# Schnittstelle_Swissphone.net
KiCad netlist of a schematic drawn in EAGLE
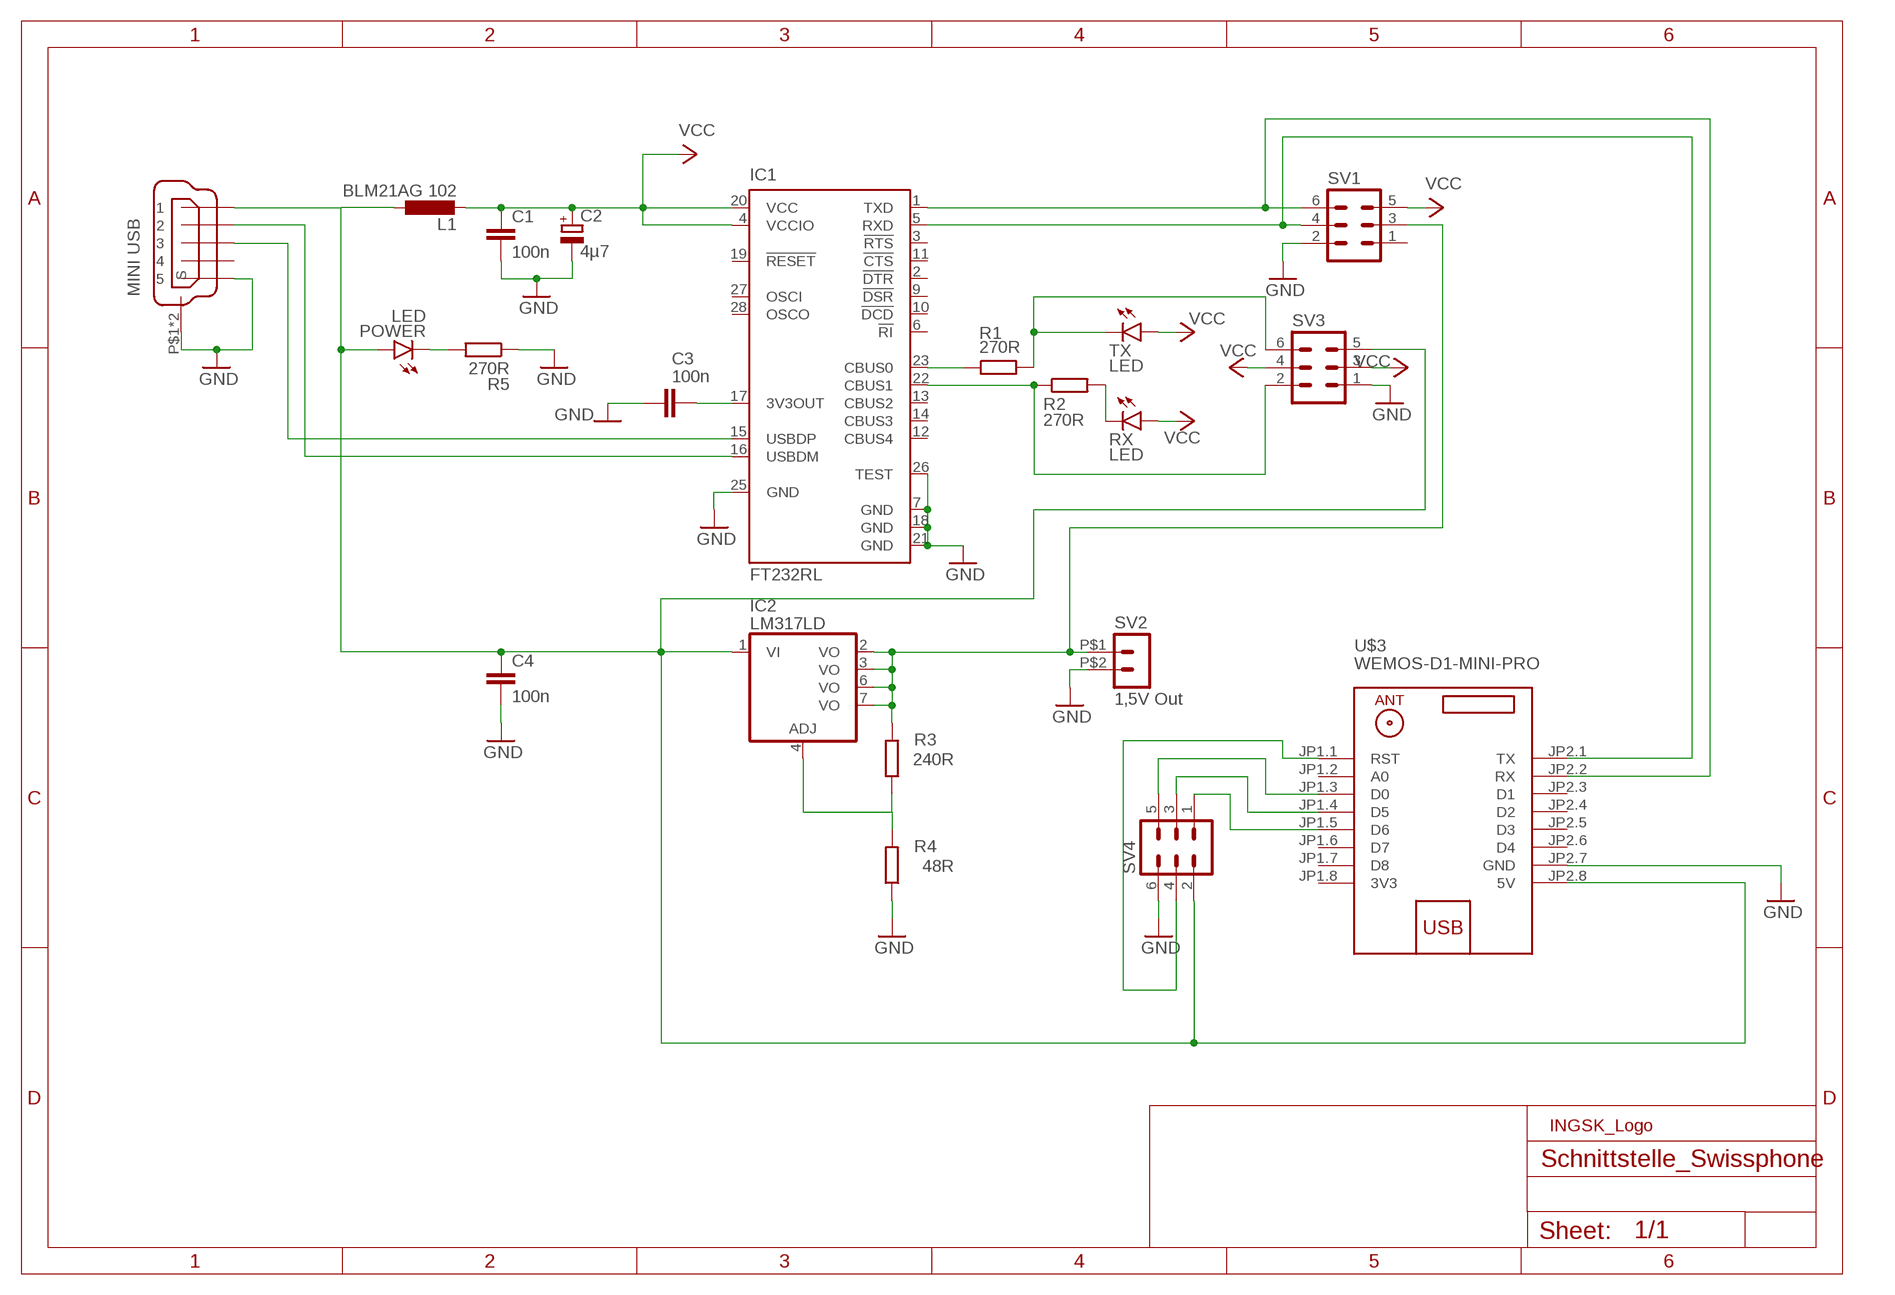
[diagram p0: schematic, sheet 1]

(export (version "E")
  (design (tool "Eeschema 10.0.6"))
  (components
    (comp (ref "C1")
      (value "100n")
      (footprint "eagle-import:C0603")
      (libsource (lib "eagle-import") (part "C-EUC0603"))
    )
    (comp (ref "C2")
      (value "4µ7")
      (footprint "eagle-import:A_3216-18W")
      (libsource (lib "eagle-import") (part "CPOL-EUA/3216-18W"))
    )
    (comp (ref "C3")
      (value "100n")
      (footprint "eagle-import:C0603")
      (libsource (lib "eagle-import") (part "C-EUC0603"))
    )
    (comp (ref "C4")
      (value "100n")
      (footprint "eagle-import:C0603")
      (libsource (lib "eagle-import") (part "C-EUC0603"))
    )
    (comp (ref "IC1")
      (value "FT232RL")
      (footprint "eagle-import:SSOP28")
      (libsource (lib "eagle-import") (part "FT232RL"))
    )
    (comp (ref "IC2")
      (value "LM317LD")
      (footprint "eagle-import:SO08")
      (libsource (lib "eagle-import") (part "LM317LD"))
    )
    (comp (ref "L1")
      (value "BLM21AG 102")
      (footprint "eagle-import:L2012C")
      (libsource (lib "eagle-import") (part "L-EUL2012C"))
    )
    (comp (ref "POWER")
      (value "LED")
      (footprint "eagle-import:LED3MM")
      (libsource (lib "eagle-import") (part "LED3MM"))
    )
    (comp (ref "R1")
      (value "270R")
      (footprint "eagle-import:R0603")
      (libsource (lib "eagle-import") (part "R-EU_R0603"))
    )
    (comp (ref "R2")
      (value "270R")
      (footprint "eagle-import:R0603")
      (libsource (lib "eagle-import") (part "R-EU_R0603"))
    )
    (comp (ref "R3")
      (value "240R")
      (footprint "eagle-import:R1206")
      (libsource (lib "eagle-import") (part "R-EU_R1206"))
    )
    (comp (ref "R4")
      (value "48R")
      (footprint "eagle-import:R1206")
      (libsource (lib "eagle-import") (part "R-EU_R1206"))
    )
    (comp (ref "R5")
      (value "270R")
      (footprint "eagle-import:R0603")
      (libsource (lib "eagle-import") (part "R-EU_R0603"))
    )
    (comp (ref "RX")
      (value "LED")
      (footprint "eagle-import:LED3MM")
      (libsource (lib "eagle-import") (part "LED3MM"))
    )
    (comp (ref "SV1")
      (value "ML6")
      (footprint "eagle-import:ML6")
      (libsource (lib "eagle-import") (part "ML6"))
    )
    (comp (ref "SV2")
      (value "1,5V Out")
      (footprint "eagle-import:43650-0200")
      (libsource (lib "eagle-import") (part "HEADER_POS2_?43650-0200"))
    )
    (comp (ref "SV3")
      (value "ML6")
      (footprint "eagle-import:ML6")
      (libsource (lib "eagle-import") (part "ML6"))
    )
    (comp (ref "SV4")
      (value "ML6")
      (footprint "eagle-import:ML6")
      (libsource (lib "eagle-import") (part "ML6"))
    )
    (comp (ref "TX")
      (value "LED")
      (footprint "eagle-import:LED3MM")
      (libsource (lib "eagle-import") (part "LED3MM"))
    )
    (comp (ref "U$1")
      (value "MINI USB")
      (footprint "eagle-import:USBBWM")
      (libsource (lib "eagle-import") (part "USBBWM"))
    )
    (comp (ref "U$2")
      (value "SK")
      (footprint "eagle-import:INGSK")
      (libsource (lib "eagle-import") (part "SK"))
    )
    (comp (ref "U$3")
      (value "WEMOS-D1-MINI-PRO")
      (footprint "eagle-import:WEMOS-D1-MINI-PRO")
      (libsource (lib "eagle-import") (part "WEMOS-D1-MINI-PRO"))
    )
  )
  (nets
    (net (code "1") (name "/3V3") (class "Default")
      (node (ref "U$3") (pin "JP1.8") (pinfunction "3V3_JP1.8") (pintype "power_in"))
    )
    (net (code "2") (name "GND") (class "Default")
      (node (ref "C1") (pin "2") (pinfunction "2_2") (pintype "passive"))
      (node (ref "C2") (pin "-") (pinfunction "-_-") (pintype "passive"))
      (node (ref "C3") (pin "2") (pinfunction "2_2") (pintype "passive"))
      (node (ref "C4") (pin "2") (pinfunction "2_2") (pintype "passive"))
      (node (ref "IC1") (pin "18") (pinfunction "GND_18") (pintype "power_in"))
      (node (ref "IC1") (pin "21") (pinfunction "GND_21") (pintype "power_in"))
      (node (ref "IC1") (pin "25") (pinfunction "GND_25") (pintype "power_in"))
      (node (ref "IC1") (pin "26") (pinfunction "TEST_26") (pintype "input"))
      (node (ref "IC1") (pin "7") (pinfunction "GND_7") (pintype "power_in"))
      (node (ref "R4") (pin "1") (pinfunction "1_1") (pintype "passive"))
      (node (ref "R5") (pin "1") (pinfunction "1_1") (pintype "passive"))
      (node (ref "SV1") (pin "2") (pinfunction "2_2") (pintype "passive"))
      (node (ref "SV2") (pin "P$2") (pinfunction "2_P$2") (pintype "passive"))
      (node (ref "SV3") (pin "1") (pinfunction "1_1") (pintype "passive"))
      (node (ref "SV4") (pin "6") (pinfunction "6_6") (pintype "passive"))
      (node (ref "U$1") (pin "P$1") (pinfunction "S_P$1") (pintype "bidirectional"))
      (node (ref "U$1") (pin "P$2") (pinfunction "S_P$2") (pintype "bidirectional"))
      (node (ref "U$1") (pin "P$3") (pinfunction "5_P$3") (pintype "passive"))
      (node (ref "U$3") (pin "JP2.7") (pinfunction "GND_JP2.7") (pintype "power_in"))
    )
    (net (code "3") (name "Net-(IC1-3V3OUT)") (class "Default")
      (node (ref "C3") (pin "1") (pinfunction "1_1") (pintype "passive"))
      (node (ref "IC1") (pin "17") (pinfunction "3V3OUT_17") (pintype "output"))
    )
    (net (code "4") (name "Net-(IC1-CBUS0)") (class "Default")
      (node (ref "IC1") (pin "23") (pinfunction "CBUS0_23") (pintype "bidirectional"))
      (node (ref "R1") (pin "1") (pinfunction "1_1") (pintype "passive"))
    )
    (net (code "5") (name "Net-(IC1-CBUS1)") (class "Default")
      (node (ref "IC1") (pin "22") (pinfunction "CBUS1_22") (pintype "bidirectional"))
      (node (ref "R2") (pin "1") (pinfunction "1_1") (pintype "passive"))
      (node (ref "SV3") (pin "2") (pinfunction "2_2") (pintype "passive"))
    )
    (net (code "6") (name "Net-(IC1-RXD)") (class "Default")
      (node (ref "IC1") (pin "5") (pinfunction "RXD_5") (pintype "input"))
      (node (ref "SV1") (pin "4") (pinfunction "4_4") (pintype "passive"))
      (node (ref "U$3") (pin "JP2.1") (pinfunction "TX_JP2.1") (pintype "bidirectional"))
    )
    (net (code "7") (name "Net-(IC1-TXD)") (class "Default")
      (node (ref "IC1") (pin "1") (pinfunction "TXD_1") (pintype "output"))
      (node (ref "SV1") (pin "6") (pinfunction "6_6") (pintype "passive"))
      (node (ref "U$3") (pin "JP2.2") (pinfunction "RX_JP2.2") (pintype "bidirectional"))
    )
    (net (code "8") (name "Net-(IC1-USBDM)") (class "Default")
      (node (ref "IC1") (pin "16") (pinfunction "USBDM_16") (pintype "bidirectional"))
      (node (ref "U$1") (pin "P$6") (pinfunction "2_P$6") (pintype "passive"))
    )
    (net (code "9") (name "Net-(IC1-USBDP)") (class "Default")
      (node (ref "IC1") (pin "15") (pinfunction "USBDP_15") (pintype "bidirectional"))
      (node (ref "U$1") (pin "P$5") (pinfunction "3_P$5") (pintype "passive"))
    )
    (net (code "10") (name "Net-(IC2-ADJ)") (class "Default")
      (node (ref "IC2") (pin "4") (pinfunction "ADJ_4") (pintype "input"))
      (node (ref "R3") (pin "1") (pinfunction "1_1") (pintype "passive"))
      (node (ref "R4") (pin "2") (pinfunction "2_2") (pintype "passive"))
    )
    (net (code "11") (name "Net-(IC2-VI)") (class "Default")
      (node (ref "C4") (pin "1") (pinfunction "1_1") (pintype "passive"))
      (node (ref "IC2") (pin "1") (pinfunction "VI_1") (pintype "input"))
      (node (ref "L1") (pin "1") (pinfunction "1_1") (pintype "passive"))
      (node (ref "POWER") (pin "A") (pinfunction "A_A") (pintype "passive"))
      (node (ref "SV3") (pin "5") (pinfunction "5_5") (pintype "passive"))
      (node (ref "SV4") (pin "2") (pinfunction "2_2") (pintype "passive"))
      (node (ref "U$1") (pin "P$7") (pinfunction "1_P$7") (pintype "passive"))
      (node (ref "U$3") (pin "JP2.8") (pinfunction "5V_JP2.8") (pintype "power_in"))
    )
    (net (code "12") (name "Net-(POWER-C)") (class "Default")
      (node (ref "POWER") (pin "K") (pinfunction "C_K") (pintype "passive"))
      (node (ref "R5") (pin "2") (pinfunction "2_2") (pintype "passive"))
    )
    (net (code "13") (name "Net-(RX-C)") (class "Default")
      (node (ref "R2") (pin "2") (pinfunction "2_2") (pintype "passive"))
      (node (ref "RX") (pin "K") (pinfunction "C_K") (pintype "passive"))
    )
    (net (code "14") (name "Net-(SV2-1)") (class "Default")
      (node (ref "IC2") (pin "2") (pinfunction "VO_2") (pintype "passive"))
      (node (ref "IC2") (pin "3") (pinfunction "VO_3") (pintype "passive"))
      (node (ref "IC2") (pin "6") (pinfunction "VO_6") (pintype "passive"))
      (node (ref "IC2") (pin "7") (pinfunction "VO_7") (pintype "passive"))
      (node (ref "R3") (pin "2") (pinfunction "2_2") (pintype "passive"))
      (node (ref "SV1") (pin "3") (pinfunction "3_3") (pintype "passive"))
      (node (ref "SV2") (pin "P$1") (pinfunction "1_P$1") (pintype "passive"))
    )
    (net (code "15") (name "Net-(TX-C)") (class "Default")
      (node (ref "R1") (pin "2") (pinfunction "2_2") (pintype "passive"))
      (node (ref "SV3") (pin "6") (pinfunction "6_6") (pintype "passive"))
      (node (ref "TX") (pin "K") (pinfunction "C_K") (pintype "passive"))
    )
    (net (code "16") (name "Net-(U$3-D0)") (class "Default")
      (node (ref "SV4") (pin "5") (pinfunction "5_5") (pintype "passive"))
      (node (ref "U$3") (pin "JP1.3") (pinfunction "D0_JP1.3") (pintype "bidirectional"))
    )
    (net (code "17") (name "Net-(U$3-D5)") (class "Default")
      (node (ref "SV4") (pin "3") (pinfunction "3_3") (pintype "passive"))
      (node (ref "U$3") (pin "JP1.4") (pinfunction "D5_JP1.4") (pintype "bidirectional"))
    )
    (net (code "18") (name "Net-(U$3-D6)") (class "Default")
      (node (ref "SV4") (pin "1") (pinfunction "1_1") (pintype "passive"))
      (node (ref "U$3") (pin "JP1.5") (pinfunction "D6_JP1.5") (pintype "bidirectional"))
    )
    (net (code "19") (name "Net-(U$3-RST)") (class "Default")
      (node (ref "SV4") (pin "4") (pinfunction "4_4") (pintype "passive"))
      (node (ref "U$3") (pin "JP1.1") (pinfunction "RST_JP1.1") (pintype "bidirectional"))
    )
    (net (code "20") (name "VCC") (class "Default")
      (node (ref "C1") (pin "1") (pinfunction "1_1") (pintype "passive"))
      (node (ref "C2") (pin "+") (pinfunction "+_+") (pintype "passive"))
      (node (ref "IC1") (pin "20") (pinfunction "VCC_20") (pintype "power_in"))
      (node (ref "IC1") (pin "4") (pinfunction "VCCIO_4") (pintype "power_in"))
      (node (ref "L1") (pin "2") (pinfunction "2_2") (pintype "passive"))
      (node (ref "RX") (pin "A") (pinfunction "A_A") (pintype "passive"))
      (node (ref "SV1") (pin "5") (pinfunction "5_5") (pintype "passive"))
      (node (ref "SV3") (pin "3") (pinfunction "3_3") (pintype "passive"))
      (node (ref "SV3") (pin "4") (pinfunction "4_4") (pintype "passive"))
      (node (ref "TX") (pin "A") (pinfunction "A_A") (pintype "passive"))
    )
    (net (code "21") (name "unconnected-(IC1-CBUS2-Pad13)") (class "Default")
      (node (ref "IC1") (pin "13") (pinfunction "CBUS2_13") (pintype "bidirectional"))
    )
    (net (code "22") (name "unconnected-(IC1-CBUS3-Pad14)") (class "Default")
      (node (ref "IC1") (pin "14") (pinfunction "CBUS3_14") (pintype "bidirectional"))
    )
    (net (code "23") (name "unconnected-(IC1-CBUS4-Pad12)") (class "Default")
      (node (ref "IC1") (pin "12") (pinfunction "CBUS4_12") (pintype "bidirectional"))
    )
    (net (code "24") (name "unconnected-(IC1-OSCI-Pad27)") (class "Default")
      (node (ref "IC1") (pin "27") (pinfunction "OSCI_27") (pintype "input"))
    )
    (net (code "25") (name "unconnected-(IC1-OSCO-Pad28)") (class "Default")
      (node (ref "IC1") (pin "28") (pinfunction "OSCO_28") (pintype "output"))
    )
    (net (code "26") (name "unconnected-(IC1-~{CTS}-Pad11)") (class "Default")
      (node (ref "IC1") (pin "11") (pinfunction "~{CTS}_11") (pintype "input"))
    )
    (net (code "27") (name "unconnected-(IC1-~{DCD}-Pad10)") (class "Default")
      (node (ref "IC1") (pin "10") (pinfunction "~{DCD}_10") (pintype "input"))
    )
    (net (code "28") (name "unconnected-(IC1-~{DSR}-Pad9)") (class "Default")
      (node (ref "IC1") (pin "9") (pinfunction "~{DSR}_9") (pintype "input"))
    )
    (net (code "29") (name "unconnected-(IC1-~{DTR}-Pad2)") (class "Default")
      (node (ref "IC1") (pin "2") (pinfunction "~{DTR}_2") (pintype "output"))
    )
    (net (code "30") (name "unconnected-(IC1-~{RESET}-Pad19)") (class "Default")
      (node (ref "IC1") (pin "19") (pinfunction "~{RESET}_19") (pintype "input"))
    )
    (net (code "31") (name "unconnected-(IC1-~{RI}-Pad6)") (class "Default")
      (node (ref "IC1") (pin "6") (pinfunction "~{RI}_6") (pintype "input"))
    )
    (net (code "32") (name "unconnected-(IC1-~{RTS}-Pad3)") (class "Default")
      (node (ref "IC1") (pin "3") (pinfunction "~{RTS}_3") (pintype "output"))
    )
    (net (code "33") (name "unconnected-(SV1-Pad1)") (class "Default")
      (node (ref "SV1") (pin "1") (pinfunction "1_1") (pintype "passive"))
    )
    (net (code "34") (name "unconnected-(U$1-4-PadP$4)") (class "Default")
      (node (ref "U$1") (pin "P$4") (pinfunction "4_P$4") (pintype "passive"))
    )
    (net (code "35") (name "unconnected-(U$3-A0-PadJP1.2)") (class "Default")
      (node (ref "U$3") (pin "JP1.2") (pinfunction "A0_JP1.2") (pintype "bidirectional"))
    )
    (net (code "36") (name "unconnected-(U$3-D1-PadJP2.3)") (class "Default")
      (node (ref "U$3") (pin "JP2.3") (pinfunction "D1_JP2.3") (pintype "bidirectional"))
    )
    (net (code "37") (name "unconnected-(U$3-D2-PadJP2.4)") (class "Default")
      (node (ref "U$3") (pin "JP2.4") (pinfunction "D2_JP2.4") (pintype "bidirectional"))
    )
    (net (code "38") (name "unconnected-(U$3-D3-PadJP2.5)") (class "Default")
      (node (ref "U$3") (pin "JP2.5") (pinfunction "D3_JP2.5") (pintype "bidirectional"))
    )
    (net (code "39") (name "unconnected-(U$3-D4-PadJP2.6)") (class "Default")
      (node (ref "U$3") (pin "JP2.6") (pinfunction "D4_JP2.6") (pintype "bidirectional"))
    )
    (net (code "40") (name "unconnected-(U$3-D7-PadJP1.6)") (class "Default")
      (node (ref "U$3") (pin "JP1.6") (pinfunction "D7_JP1.6") (pintype "bidirectional"))
    )
    (net (code "41") (name "unconnected-(U$3-D8-PadJP1.7)") (class "Default")
      (node (ref "U$3") (pin "JP1.7") (pinfunction "D8_JP1.7") (pintype "bidirectional"))
    )
  )
)
